# USB_Programmer.net
KiCad netlist of a schematic drawn in Altium Designer
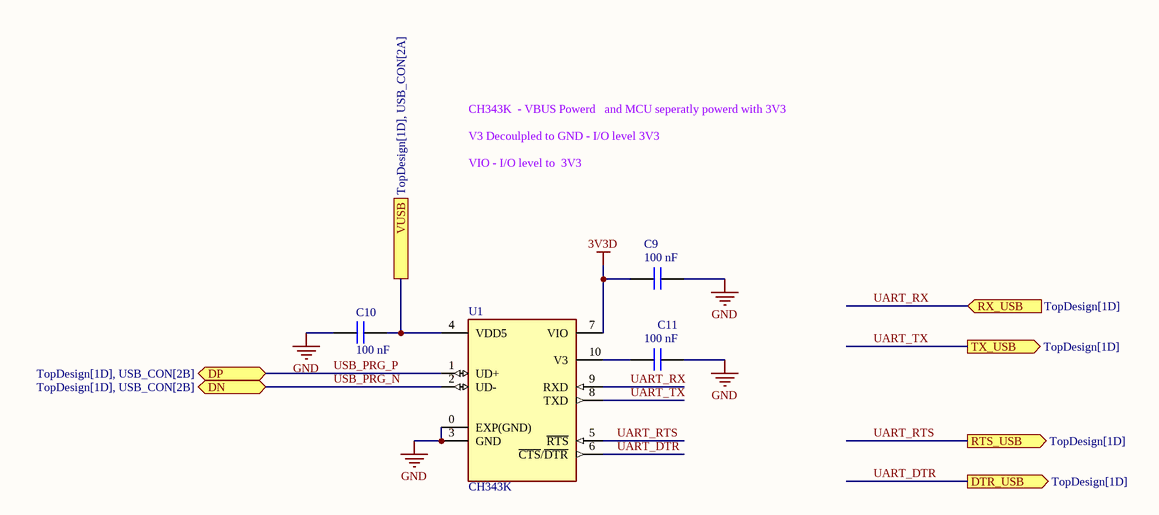
[diagram p0: USB_Programmer.SchDoc]

(export (version "E")
  (design (tool "Eeschema 10.0.6"))
  (components
    (comp (ref "C9")
      (value "100 nF")
      (footprint "CAP_0603")
      (description "Cap SMD.")
      (libsource (lib "Aptinex_discrete") (part "Cap SMD"))
    )
    (comp (ref "C10")
      (value "100 nF")
      (footprint "CAP_0603")
      (description "Cap SMD.")
      (libsource (lib "Aptinex_discrete") (part "Cap SMD"))
    )
    (comp (ref "C11")
      (value "100 nF")
      (footprint "CAP_0603")
      (description "Cap SMD.")
      (libsource (lib "Aptinex_discrete") (part "Cap SMD"))
    )
    (comp (ref "U1")
      (value "CH343K")
      (footprint "CH343K")
      (description "USB to UART USB 2.0 ESSOP-10-150mil-1mm Interface Controllers ROHS")
      (fields (field (name "MF") "WCH"))
      (libsource (lib "Aptinex_devices") (part "CH343K"))
    )
  )
  (nets
    (net (code "1") (name "/UART_DTR") (class "Default")
      (node (ref "U1") (pin "6") (pinfunction "~{CTS}/~{DTR}_6") (pintype "output"))
    )
    (net (code "2") (name "/UART_RTS") (class "Default")
      (node (ref "U1") (pin "5") (pinfunction "~{RTS}_5") (pintype "input"))
    )
    (net (code "3") (name "/UART_RX") (class "Default")
      (node (ref "U1") (pin "9") (pinfunction "RXD_9") (pintype "input"))
    )
    (net (code "4") (name "/UART_TX") (class "Default")
      (node (ref "U1") (pin "8") (pinfunction "TXD_8") (pintype "output"))
    )
    (net (code "5") (name "/USB_PRG_N") (class "Default")
      (node (ref "U1") (pin "2") (pinfunction "UD-_2") (pintype "bidirectional"))
    )
    (net (code "6") (name "/USB_PRG_P") (class "Default")
      (node (ref "U1") (pin "1") (pinfunction "UD+_1") (pintype "bidirectional"))
    )
    (net (code "7") (name "/VUSB") (class "Default")
      (node (ref "C10") (pin "1") (pinfunction "1_1") (pintype "passive"))
      (node (ref "U1") (pin "4") (pinfunction "VDD5_4") (pintype "passive"))
    )
    (net (code "8") (name "3V3D") (class "Default")
      (node (ref "C9") (pin "2") (pinfunction "2_2") (pintype "passive"))
      (node (ref "U1") (pin "7") (pinfunction "VIO_7") (pintype "power_in"))
    )
    (net (code "9") (name "GND") (class "Default")
      (node (ref "C10") (pin "2") (pinfunction "2_2") (pintype "passive"))
      (node (ref "C11") (pin "1") (pinfunction "1_1") (pintype "passive"))
      (node (ref "C9") (pin "1") (pinfunction "1_1") (pintype "passive"))
      (node (ref "U1") (pin "0") (pinfunction "EXP(GND)_0") (pintype "power_in"))
      (node (ref "U1") (pin "3") (pinfunction "GND_3") (pintype "power_in"))
    )
    (net (code "10") (name "Net-(U1-V3)") (class "Default")
      (node (ref "C11") (pin "2") (pinfunction "2_2") (pintype "passive"))
      (node (ref "U1") (pin "10") (pinfunction "V3_10") (pintype "power_in"))
    )
  )
)
